# TPT02_tentative.net
KiCad netlist of a schematic drawn in EAGLE
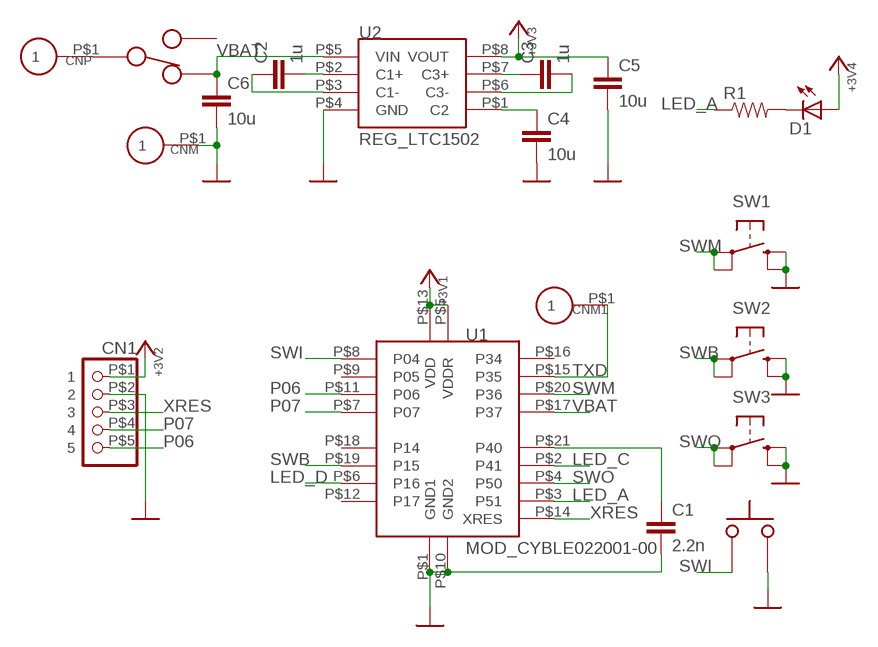
[diagram p0: schematic, sheet 1]

(export (version "E")
  (design (tool "Eeschema 10.0.6"))
  (components
    (comp (ref "C1")
      (value "2.2n")
      (footprint "eagle-import:0603")
      (libsource (lib "eagle-import") (part "CAP0603"))
    )
    (comp (ref "C2")
      (value "1u")
      (footprint "eagle-import:0603")
      (libsource (lib "eagle-import") (part "CAP0603"))
    )
    (comp (ref "C3")
      (value "1u")
      (footprint "eagle-import:0603")
      (libsource (lib "eagle-import") (part "CAP0603"))
    )
    (comp (ref "C4")
      (value "10u")
      (footprint "eagle-import:0603")
      (libsource (lib "eagle-import") (part "CAP0603"))
    )
    (comp (ref "C5")
      (value "10u")
      (footprint "eagle-import:0603")
      (libsource (lib "eagle-import") (part "CAP0603"))
    )
    (comp (ref "C6")
      (value "10u")
      (footprint "eagle-import:0603")
      (libsource (lib "eagle-import") (part "CAP0603"))
    )
    (comp (ref "CN1")
      (value "CON_PINHD-1X550MIL")
      (footprint "eagle-import:1X5_50MIL")
      (libsource (lib "eagle-import") (part "CON_PINHD-1X550MIL"))
    )
    (comp (ref "CNM")
      (value "CON_P01SMD1MM")
      (footprint "eagle-import:PAD_SMD1MM")
      (libsource (lib "eagle-import") (part "CON_P01SMD1MM"))
    )
    (comp (ref "CNM1")
      (value "CON_P01SMD1MM")
      (footprint "eagle-import:PAD_SMD1MM")
      (libsource (lib "eagle-import") (part "CON_P01SMD1MM"))
    )
    (comp (ref "CNP")
      (value "CON_P01SMD1MM")
      (footprint "eagle-import:PAD_SMD1MM")
      (libsource (lib "eagle-import") (part "CON_P01SMD1MM"))
    )
    (comp (ref "D1")
      (value "LED0603")
      (footprint "eagle-import:SPARKFUN_LED-0603")
      (libsource (lib "eagle-import") (part "LED0603"))
    )
    (comp (ref "R1")
      (value "RES0603")
      (footprint "eagle-import:0603")
      (libsource (lib "eagle-import") (part "RES0603"))
    )
    (comp (ref "SW1")
      (value "SW_TACTEVQP2")
      (footprint "eagle-import:SW_EVQP2")
      (libsource (lib "eagle-import") (part "SW_TACTEVQP2"))
    )
    (comp (ref "SW2")
      (value "SW_TACTTVAF17")
      (footprint "eagle-import:SW_TVF17")
      (libsource (lib "eagle-import") (part "SW_TACTTVAF17"))
    )
    (comp (ref "SW3")
      (value "SW_TACTTVAF17")
      (footprint "eagle-import:SW_TVF17")
      (libsource (lib "eagle-import") (part "SW_TACTTVAF17"))
    )
    (comp (ref "SW4")
      (value "SW_SLIDECUS12")
      (footprint "eagle-import:SW_CUS-12B")
      (libsource (lib "eagle-import") (part "SW_SLIDECUS12"))
    )
    (comp (ref "SW6")
      (value "SW_TACT2PB3U3000")
      (footprint "eagle-import:SW_B3U-3000P")
      (libsource (lib "eagle-import") (part "SW_TACT2PB3U3000"))
    )
    (comp (ref "U1")
      (value "MOD_CYBLE022001-00")
      (footprint "eagle-import:MOD_CYBLE022001-00")
      (libsource (lib "eagle-import") (part "MOD_CYBLE022001-00"))
    )
    (comp (ref "U2")
      (value "REG_LTC1502")
      (footprint "eagle-import:MSOP8")
      (libsource (lib "eagle-import") (part "REG_LTC1502"))
    )
  )
  (nets
    (net (code "1") (name "/LED_A") (class "Default")
      (node (ref "R1") (pin "1") (pinfunction "1_1") (pintype "passive"))
      (node (ref "U1") (pin "P$3") (pinfunction "P51_P$3") (pintype "bidirectional"))
    )
    (net (code "2") (name "/LED_C") (class "Default")
      (node (ref "U1") (pin "P$2") (pinfunction "P41_P$2") (pintype "bidirectional"))
    )
    (net (code "3") (name "/LED_D") (class "Default")
      (node (ref "U1") (pin "P$6") (pinfunction "P16_P$6") (pintype "bidirectional"))
    )
    (net (code "4") (name "/P$3") (class "Default")
      (node (ref "SW4") (pin "P$3") (pinfunction "P$3_P$3") (pintype "power_in"))
    )
    (net (code "5") (name "/P06") (class "Default")
      (node (ref "CN1") (pin "P$5") (pinfunction "5_P$5") (pintype "passive"))
      (node (ref "U1") (pin "P$11") (pinfunction "P06_P$11") (pintype "bidirectional"))
    )
    (net (code "6") (name "/P07") (class "Default")
      (node (ref "CN1") (pin "P$4") (pinfunction "4_P$4") (pintype "passive"))
      (node (ref "U1") (pin "P$7") (pinfunction "P07_P$7") (pintype "bidirectional"))
    )
    (net (code "7") (name "/SWB") (class "Default")
      (node (ref "SW2") (pin "P$1") (pinfunction "P_P$1") (pintype "passive"))
      (node (ref "SW2") (pin "P$2") (pinfunction "P1_P$2") (pintype "passive"))
      (node (ref "U1") (pin "P$19") (pinfunction "P15_P$19") (pintype "bidirectional"))
    )
    (net (code "8") (name "/SWI") (class "Default")
      (node (ref "SW6") (pin "P$2") (pinfunction "P$2_P$2") (pintype "passive"))
      (node (ref "U1") (pin "P$8") (pinfunction "P04_P$8") (pintype "bidirectional"))
    )
    (net (code "9") (name "/SWM") (class "Default")
      (node (ref "SW1") (pin "PA1") (pinfunction "P_PA1") (pintype "passive"))
      (node (ref "SW1") (pin "PA2") (pinfunction "P1_PA2") (pintype "passive"))
      (node (ref "U1") (pin "P$20") (pinfunction "P36_P$20") (pintype "bidirectional"))
    )
    (net (code "10") (name "/SWO") (class "Default")
      (node (ref "SW3") (pin "P$1") (pinfunction "P_P$1") (pintype "passive"))
      (node (ref "SW3") (pin "P$2") (pinfunction "P1_P$2") (pintype "passive"))
      (node (ref "U1") (pin "P$4") (pinfunction "P50_P$4") (pintype "bidirectional"))
    )
    (net (code "11") (name "/TXD") (class "Default")
      (node (ref "CNM1") (pin "P$1") (pinfunction "1_P$1") (pintype "bidirectional"))
      (node (ref "U1") (pin "P$15") (pinfunction "P35_P$15") (pintype "bidirectional"))
    )
    (net (code "12") (name "/VBAT") (class "Default")
      (node (ref "C6") (pin "1") (pinfunction "1_1") (pintype "passive"))
      (node (ref "SW4") (pin "P$1") (pinfunction "P$1_P$1") (pintype "power_in"))
      (node (ref "U1") (pin "P$17") (pinfunction "P37_P$17") (pintype "bidirectional"))
      (node (ref "U2") (pin "P$5") (pinfunction "VIN_P$5") (pintype "bidirectional"))
    )
    (net (code "13") (name "/XRES") (class "Default")
      (node (ref "CN1") (pin "P$3") (pinfunction "3_P$3") (pintype "passive"))
      (node (ref "U1") (pin "P$14") (pinfunction "XRES_P$14") (pintype "bidirectional"))
    )
    (net (code "14") (name "Net-(CNP-1)") (class "Default")
      (node (ref "CNP") (pin "P$1") (pinfunction "1_P$1") (pintype "bidirectional"))
      (node (ref "SW4") (pin "P$2") (pinfunction "P$2_P$2") (pintype "power_in"))
    )
    (net (code "15") (name "Net-(D1-PadC)") (class "Default")
      (node (ref "D1") (pin "C") (pinfunction "C_C") (pintype "passive"))
      (node (ref "R1") (pin "2") (pinfunction "2_2") (pintype "passive"))
    )
    (net (code "16") (name "Net-(U1-P40)") (class "Default")
      (node (ref "C1") (pin "1") (pinfunction "1_1") (pintype "passive"))
      (node (ref "U1") (pin "P$21") (pinfunction "P40_P$21") (pintype "bidirectional"))
    )
    (net (code "17") (name "Net-(U2-C1+)") (class "Default")
      (node (ref "C2") (pin "2") (pinfunction "2_2") (pintype "passive"))
      (node (ref "U2") (pin "P$2") (pinfunction "C1+_P$2") (pintype "bidirectional"))
    )
    (net (code "18") (name "Net-(U2-C1-)") (class "Default")
      (node (ref "C2") (pin "1") (pinfunction "1_1") (pintype "passive"))
      (node (ref "U2") (pin "P$3") (pinfunction "C1-_P$3") (pintype "bidirectional"))
    )
    (net (code "19") (name "Net-(U2-C2)") (class "Default")
      (node (ref "C4") (pin "1") (pinfunction "1_1") (pintype "passive"))
      (node (ref "U2") (pin "P$1") (pinfunction "C2_P$1") (pintype "bidirectional"))
    )
    (net (code "20") (name "Net-(U2-C3+)") (class "Default")
      (node (ref "C3") (pin "1") (pinfunction "1_1") (pintype "passive"))
      (node (ref "U2") (pin "P$7") (pinfunction "C3+_P$7") (pintype "bidirectional"))
    )
    (net (code "21") (name "Net-(U2-C3-)") (class "Default")
      (node (ref "C3") (pin "2") (pinfunction "2_2") (pintype "passive"))
      (node (ref "U2") (pin "P$6") (pinfunction "C3-_P$6") (pintype "bidirectional"))
    )
    (net (code "22") (name "POW_+3V3") (class "Default")
      (node (ref "C5") (pin "1") (pinfunction "1_1") (pintype "passive"))
      (node (ref "CN1") (pin "P$1") (pinfunction "1_P$1") (pintype "passive"))
      (node (ref "D1") (pin "A") (pinfunction "A_A") (pintype "passive"))
      (node (ref "U1") (pin "P$13") (pinfunction "VDD_P$13") (pintype "bidirectional"))
      (node (ref "U1") (pin "P$5") (pinfunction "VDDR_P$5") (pintype "bidirectional"))
      (node (ref "U2") (pin "P$8") (pinfunction "VOUT_P$8") (pintype "bidirectional"))
    )
    (net (code "23") (name "POW_GND") (class "Default")
      (node (ref "C1") (pin "2") (pinfunction "2_2") (pintype "passive"))
      (node (ref "C4") (pin "2") (pinfunction "2_2") (pintype "passive"))
      (node (ref "C5") (pin "2") (pinfunction "2_2") (pintype "passive"))
      (node (ref "C6") (pin "2") (pinfunction "2_2") (pintype "passive"))
      (node (ref "CN1") (pin "P$2") (pinfunction "2_P$2") (pintype "passive"))
      (node (ref "CNM") (pin "P$1") (pinfunction "1_P$1") (pintype "bidirectional"))
      (node (ref "SW1") (pin "PB1") (pinfunction "S_PB1") (pintype "passive"))
      (node (ref "SW1") (pin "PB2") (pinfunction "S1_PB2") (pintype "passive"))
      (node (ref "SW2") (pin "P$3") (pinfunction "S_P$3") (pintype "passive"))
      (node (ref "SW2") (pin "P$4") (pinfunction "S1_P$4") (pintype "passive"))
      (node (ref "SW3") (pin "P$3") (pinfunction "S_P$3") (pintype "passive"))
      (node (ref "SW3") (pin "P$4") (pinfunction "S1_P$4") (pintype "passive"))
      (node (ref "SW6") (pin "P$1") (pinfunction "P$1_P$1") (pintype "passive"))
      (node (ref "U1") (pin "P$1") (pinfunction "GND1_P$1") (pintype "bidirectional"))
      (node (ref "U1") (pin "P$10") (pinfunction "GND2_P$10") (pintype "bidirectional"))
      (node (ref "U2") (pin "P$4") (pinfunction "GND_P$4") (pintype "bidirectional"))
    )
    (net (code "24") (name "unconnected-(U1-P05-PadP$9)") (class "Default")
      (node (ref "U1") (pin "P$9") (pinfunction "P05_P$9") (pintype "bidirectional"))
    )
    (net (code "25") (name "unconnected-(U1-P14-PadP$18)") (class "Default")
      (node (ref "U1") (pin "P$18") (pinfunction "P14_P$18") (pintype "bidirectional"))
    )
    (net (code "26") (name "unconnected-(U1-P17-PadP$12)") (class "Default")
      (node (ref "U1") (pin "P$12") (pinfunction "P17_P$12") (pintype "bidirectional"))
    )
    (net (code "27") (name "unconnected-(U1-P34-PadP$16)") (class "Default")
      (node (ref "U1") (pin "P$16") (pinfunction "P34_P$16") (pintype "bidirectional"))
    )
  )
)
